# design.net
KiCad netlist of a schematic drawn in EAGLE
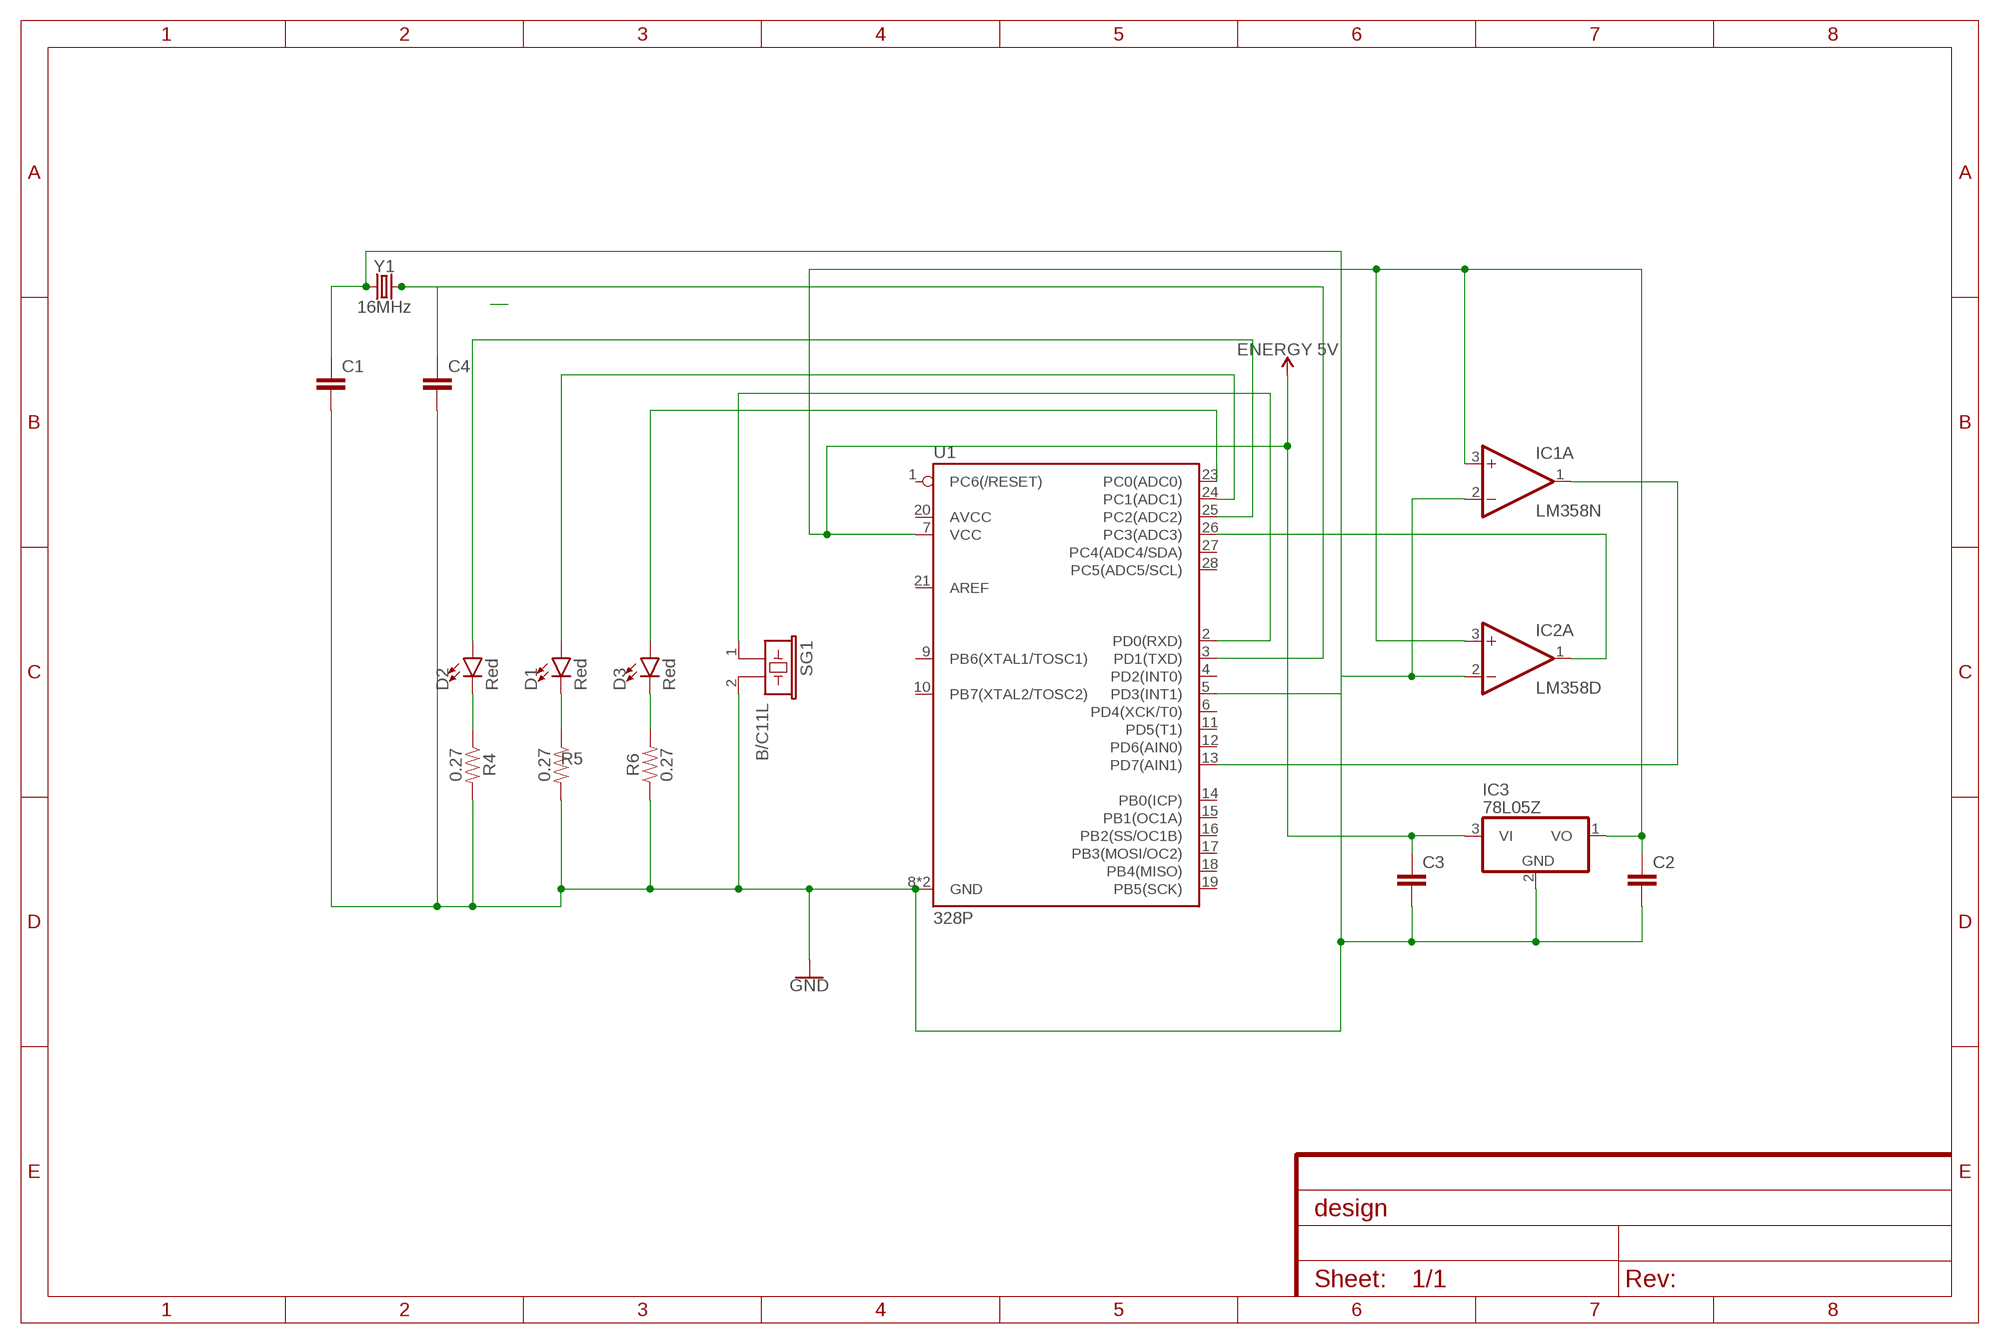
[diagram p0: schematic, sheet 1]

(export (version "E")
  (design (tool "Eeschema 10.0.6"))
  (components
    (comp (ref "C1")
      (value "C2,5-3")
      (footprint "eagle-import:C2.5-3")
      (libsource (lib "eagle-import") (part "C2,5-3"))
    )
    (comp (ref "C2")
      (value "C2,5-3")
      (footprint "eagle-import:C2.5-3")
      (libsource (lib "eagle-import") (part "C2,5-3"))
    )
    (comp (ref "C3")
      (value "C2,5-3")
      (footprint "eagle-import:C2.5-3")
      (libsource (lib "eagle-import") (part "C2,5-3"))
    )
    (comp (ref "C4")
      (value "C2,5-3")
      (footprint "eagle-import:C2.5-3")
      (libsource (lib "eagle-import") (part "C2,5-3"))
    )
    (comp (ref "D1")
      (value "Red")
      (footprint "eagle-import:LED-0603")
      (libsource (lib "eagle-import") (part "LED-RED-0603-WE"))
    )
    (comp (ref "D2")
      (value "Red")
      (footprint "eagle-import:LED-0603")
      (libsource (lib "eagle-import") (part "LED-RED-0603-WE"))
    )
    (comp (ref "D3")
      (value "Red")
      (footprint "eagle-import:LED-0603")
      (libsource (lib "eagle-import") (part "LED-RED-0603-WE"))
    )
    (comp (ref "IC1")
      (value "LM358N")
      (footprint "eagle-import:DIL08")
      (libsource (lib "eagle-import") (part "LM358N"))
    )
    (comp (ref "IC2")
      (value "LM358D")
      (footprint "eagle-import:SO08")
      (libsource (lib "eagle-import") (part "LM358D"))
    )
    (comp (ref "IC3")
      (value "78L05Z")
      (footprint "eagle-import:TO92")
      (libsource (lib "eagle-import") (part "78ZL05"))
    )
    (comp (ref "R4")
      (value "0.27")
      (footprint "eagle-import:0603")
      (libsource (lib "eagle-import") (part "0.27OHM-0603-1/10W-1%"))
    )
    (comp (ref "R5")
      (value "0.27")
      (footprint "eagle-import:0603")
      (libsource (lib "eagle-import") (part "0.27OHM-0603-1/10W-1%"))
    )
    (comp (ref "R6")
      (value "0.27")
      (footprint "eagle-import:0603")
      (libsource (lib "eagle-import") (part "0.27OHM-0603-1/10W-1%"))
    )
    (comp (ref "SG1")
      (value "B/C11L")
      (footprint "eagle-import:B_C11L")
      (libsource (lib "eagle-import") (part "B/C11L"))
    )
    (comp (ref "U1")
      (value "328P")
      (footprint "eagle-import:DIP28")
      (libsource (lib "eagle-import") (part "ATMEGA328P_PDIP"))
    )
    (comp (ref "Y1")
      (value "16MHz")
      (footprint "eagle-import:HC49US")
      (libsource (lib "eagle-import") (part "CRYSTAL-16MHZPTH-HC49US"))
    )
  )
  (nets
    (net (code "1") (name "ENERGY 5V") (class "Default")
      (node (ref "C2") (pin "1") (pinfunction "1_1") (pintype "passive"))
      (node (ref "C3") (pin "1") (pinfunction "1_1") (pintype "passive"))
      (node (ref "IC1") (pin "3") (pinfunction "+IN_3") (pintype "input"))
      (node (ref "IC2") (pin "3") (pinfunction "+IN_3") (pintype "input"))
      (node (ref "IC3") (pin "1") (pinfunction "VO_1") (pintype "passive"))
      (node (ref "IC3") (pin "3") (pinfunction "VI_3") (pintype "input"))
      (node (ref "U1") (pin "7") (pinfunction "VCC_7") (pintype "bidirectional"))
    )
    (net (code "2") (name "GND") (class "Default")
      (node (ref "C1") (pin "2") (pinfunction "2_2") (pintype "passive"))
      (node (ref "C2") (pin "2") (pinfunction "2_2") (pintype "passive"))
      (node (ref "C3") (pin "2") (pinfunction "2_2") (pintype "passive"))
      (node (ref "C4") (pin "2") (pinfunction "2_2") (pintype "passive"))
      (node (ref "IC1") (pin "2") (pinfunction "-IN_2") (pintype "input"))
      (node (ref "IC2") (pin "2") (pinfunction "-IN_2") (pintype "input"))
      (node (ref "IC3") (pin "2") (pinfunction "GND_2") (pintype "passive"))
      (node (ref "R4") (pin "2") (pinfunction "2_2") (pintype "passive"))
      (node (ref "R5") (pin "2") (pinfunction "2_2") (pintype "passive"))
      (node (ref "R6") (pin "1") (pinfunction "1_1") (pintype "passive"))
      (node (ref "SG1") (pin "2") (pinfunction "2_2") (pintype "passive"))
      (node (ref "U1") (pin "22") (pinfunction "GND_22") (pintype "bidirectional"))
      (node (ref "U1") (pin "8") (pinfunction "GND_8") (pintype "bidirectional"))
    )
    (net (code "3") (name "Net-(D1-PadC)") (class "Default")
      (node (ref "D1") (pin "C") (pinfunction "C_C") (pintype "passive"))
      (node (ref "R5") (pin "1") (pinfunction "1_1") (pintype "passive"))
    )
    (net (code "4") (name "Net-(D2-PadC)") (class "Default")
      (node (ref "D2") (pin "C") (pinfunction "C_C") (pintype "passive"))
      (node (ref "R4") (pin "1") (pinfunction "1_1") (pintype "passive"))
    )
    (net (code "5") (name "Net-(D3-PadC)") (class "Default")
      (node (ref "D3") (pin "C") (pinfunction "C_C") (pintype "passive"))
      (node (ref "R6") (pin "2") (pinfunction "2_2") (pintype "passive"))
    )
    (net (code "6") (name "Net-(IC1A-OUT)") (class "Default")
      (node (ref "IC1") (pin "1") (pinfunction "OUT_1") (pintype "output"))
      (node (ref "U1") (pin "13") (pinfunction "PD7(AIN1)_13") (pintype "bidirectional"))
    )
    (net (code "7") (name "Net-(IC2A-OUT)") (class "Default")
      (node (ref "IC2") (pin "1") (pinfunction "OUT_1") (pintype "output"))
      (node (ref "U1") (pin "26") (pinfunction "PC3(ADC3)_26") (pintype "bidirectional"))
    )
    (net (code "8") (name "Net-(U1-PC0(ADC0))") (class "Default")
      (node (ref "D3") (pin "A") (pinfunction "A_A") (pintype "passive"))
      (node (ref "U1") (pin "23") (pinfunction "PC0(ADC0)_23") (pintype "bidirectional"))
    )
    (net (code "9") (name "Net-(U1-PC1(ADC1))") (class "Default")
      (node (ref "D1") (pin "A") (pinfunction "A_A") (pintype "passive"))
      (node (ref "U1") (pin "24") (pinfunction "PC1(ADC1)_24") (pintype "bidirectional"))
    )
    (net (code "10") (name "Net-(U1-PC2(ADC2))") (class "Default")
      (node (ref "D2") (pin "A") (pinfunction "A_A") (pintype "passive"))
      (node (ref "U1") (pin "25") (pinfunction "PC2(ADC2)_25") (pintype "bidirectional"))
    )
    (net (code "11") (name "Net-(U1-PD0(RXD))") (class "Default")
      (node (ref "SG1") (pin "1") (pinfunction "1_1") (pintype "passive"))
      (node (ref "U1") (pin "2") (pinfunction "PD0(RXD)_2") (pintype "bidirectional"))
    )
    (net (code "12") (name "Net-(U1-PD1(TXD))") (class "Default")
      (node (ref "C4") (pin "1") (pinfunction "1_1") (pintype "passive"))
      (node (ref "U1") (pin "3") (pinfunction "PD1(TXD)_3") (pintype "bidirectional"))
      (node (ref "Y1") (pin "2") (pinfunction "2_2") (pintype "passive"))
    )
    (net (code "13") (name "Net-(U1-PD3(INT1))") (class "Default")
      (node (ref "C1") (pin "1") (pinfunction "1_1") (pintype "passive"))
      (node (ref "U1") (pin "5") (pinfunction "PD3(INT1)_5") (pintype "bidirectional"))
      (node (ref "Y1") (pin "1") (pinfunction "1_1") (pintype "passive"))
    )
    (net (code "14") (name "unconnected-(U1-AREF-Pad21)") (class "Default")
      (node (ref "U1") (pin "21") (pinfunction "AREF_21") (pintype "bidirectional"))
    )
    (net (code "15") (name "unconnected-(U1-AVCC-Pad20)") (class "Default")
      (node (ref "U1") (pin "20") (pinfunction "AVCC_20") (pintype "bidirectional"))
    )
    (net (code "16") (name "unconnected-(U1-PB0(ICP)-Pad14)") (class "Default")
      (node (ref "U1") (pin "14") (pinfunction "PB0(ICP)_14") (pintype "bidirectional"))
    )
    (net (code "17") (name "unconnected-(U1-PB1(OC1A)-Pad15)") (class "Default")
      (node (ref "U1") (pin "15") (pinfunction "PB1(OC1A)_15") (pintype "bidirectional"))
    )
    (net (code "18") (name "unconnected-(U1-PB2(SS{slash}OC1B)-Pad16)") (class "Default")
      (node (ref "U1") (pin "16") (pinfunction "PB2(SS/OC1B)_16") (pintype "bidirectional"))
    )
    (net (code "19") (name "unconnected-(U1-PB3(MOSI{slash}OC2)-Pad17)") (class "Default")
      (node (ref "U1") (pin "17") (pinfunction "PB3(MOSI/OC2)_17") (pintype "bidirectional"))
    )
    (net (code "20") (name "unconnected-(U1-PB4(MISO)-Pad18)") (class "Default")
      (node (ref "U1") (pin "18") (pinfunction "PB4(MISO)_18") (pintype "bidirectional"))
    )
    (net (code "21") (name "unconnected-(U1-PB5(SCK)-Pad19)") (class "Default")
      (node (ref "U1") (pin "19") (pinfunction "PB5(SCK)_19") (pintype "bidirectional"))
    )
    (net (code "22") (name "unconnected-(U1-PB6(XTAL1{slash}TOSC1)-Pad9)") (class "Default")
      (node (ref "U1") (pin "9") (pinfunction "PB6(XTAL1/TOSC1)_9") (pintype "bidirectional"))
    )
    (net (code "23") (name "unconnected-(U1-PB7(XTAL2{slash}TOSC2)-Pad10)") (class "Default")
      (node (ref "U1") (pin "10") (pinfunction "PB7(XTAL2/TOSC2)_10") (pintype "bidirectional"))
    )
    (net (code "24") (name "unconnected-(U1-PC4(ADC4{slash}SDA)-Pad27)") (class "Default")
      (node (ref "U1") (pin "27") (pinfunction "PC4(ADC4/SDA)_27") (pintype "bidirectional"))
    )
    (net (code "25") (name "unconnected-(U1-PC5(ADC5{slash}SCL)-Pad28)") (class "Default")
      (node (ref "U1") (pin "28") (pinfunction "PC5(ADC5/SCL)_28") (pintype "bidirectional"))
    )
    (net (code "26") (name "unconnected-(U1-PC6({slash}RESET)-Pad1)") (class "Default")
      (node (ref "U1") (pin "1") (pinfunction "PC6(/RESET)_1") (pintype "bidirectional"))
    )
    (net (code "27") (name "unconnected-(U1-PD2(INT0)-Pad4)") (class "Default")
      (node (ref "U1") (pin "4") (pinfunction "PD2(INT0)_4") (pintype "bidirectional"))
    )
    (net (code "28") (name "unconnected-(U1-PD4(XCK{slash}T0)-Pad6)") (class "Default")
      (node (ref "U1") (pin "6") (pinfunction "PD4(XCK/T0)_6") (pintype "bidirectional"))
    )
    (net (code "29") (name "unconnected-(U1-PD5(T1)-Pad11)") (class "Default")
      (node (ref "U1") (pin "11") (pinfunction "PD5(T1)_11") (pintype "bidirectional"))
    )
    (net (code "30") (name "unconnected-(U1-PD6(AIN0)-Pad12)") (class "Default")
      (node (ref "U1") (pin "12") (pinfunction "PD6(AIN0)_12") (pintype "bidirectional"))
    )
  )
)
